# pattern-test-board.net
KiCad netlist of a schematic drawn in EAGLE
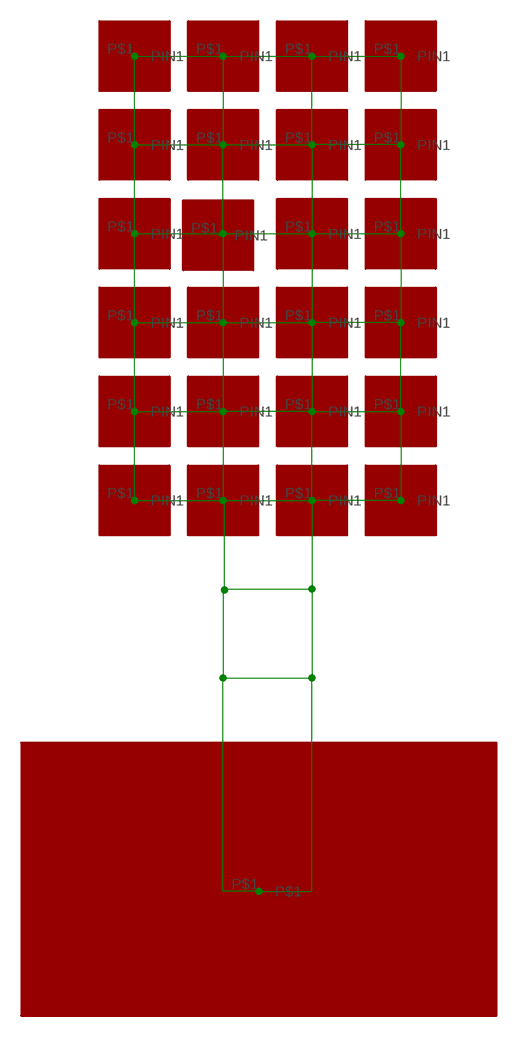
[diagram p0: schematic, sheet 1]

(export (version "E")
  (design (tool "Eeschema 10.0.6"))
  (components
    (comp (ref "U$1")
      (value "TOUCHPIN")
      (footprint "eagle-import:TOUCHPOINT")
      (libsource (lib "eagle-import") (part "TOUCHPIN"))
    )
    (comp (ref "U$2")
      (value "TOUCHPIN")
      (footprint "eagle-import:TOUCHPOINT")
      (libsource (lib "eagle-import") (part "TOUCHPIN"))
    )
    (comp (ref "U$3")
      (value "TOUCHPIN")
      (footprint "eagle-import:TOUCHPOINT")
      (libsource (lib "eagle-import") (part "TOUCHPIN"))
    )
    (comp (ref "U$4")
      (value "TOUCHPIN")
      (footprint "eagle-import:TOUCHPOINT")
      (libsource (lib "eagle-import") (part "TOUCHPIN"))
    )
    (comp (ref "U$5")
      (value "TOUCHPIN")
      (footprint "eagle-import:TOUCHPOINT")
      (libsource (lib "eagle-import") (part "TOUCHPIN"))
    )
    (comp (ref "U$6")
      (value "TOUCHPIN")
      (footprint "eagle-import:TOUCHPOINT")
      (libsource (lib "eagle-import") (part "TOUCHPIN"))
    )
    (comp (ref "U$7")
      (value "TOUCHPIN")
      (footprint "eagle-import:TOUCHPOINT")
      (libsource (lib "eagle-import") (part "TOUCHPIN"))
    )
    (comp (ref "U$8")
      (value "TOUCHPIN")
      (footprint "eagle-import:TOUCHPOINT")
      (libsource (lib "eagle-import") (part "TOUCHPIN"))
    )
    (comp (ref "U$9")
      (value "TOUCHPIN")
      (footprint "eagle-import:TOUCHPOINT")
      (libsource (lib "eagle-import") (part "TOUCHPIN"))
    )
    (comp (ref "U$14")
      (value "TOUCHPIN")
      (footprint "eagle-import:TOUCHPOINT")
      (libsource (lib "eagle-import") (part "TOUCHPIN"))
    )
    (comp (ref "U$15")
      (value "TOUCHPIN")
      (footprint "eagle-import:TOUCHPOINT")
      (libsource (lib "eagle-import") (part "TOUCHPIN"))
    )
    (comp (ref "U$16")
      (value "TOUCHPIN")
      (footprint "eagle-import:TOUCHPOINT")
      (libsource (lib "eagle-import") (part "TOUCHPIN"))
    )
    (comp (ref "U$17")
      (value "TOUCHPIN")
      (footprint "eagle-import:TOUCHPOINT")
      (libsource (lib "eagle-import") (part "TOUCHPIN"))
    )
    (comp (ref "U$18")
      (value "TOUCHPIN")
      (footprint "eagle-import:TOUCHPOINT")
      (libsource (lib "eagle-import") (part "TOUCHPIN"))
    )
    (comp (ref "U$19")
      (value "TOUCHPIN")
      (footprint "eagle-import:TOUCHPOINT")
      (libsource (lib "eagle-import") (part "TOUCHPIN"))
    )
    (comp (ref "U$20")
      (value "TOUCHPIN")
      (footprint "eagle-import:TOUCHPOINT")
      (libsource (lib "eagle-import") (part "TOUCHPIN"))
    )
    (comp (ref "U$21")
      (value "TOUCHPIN")
      (footprint "eagle-import:TOUCHPOINT")
      (libsource (lib "eagle-import") (part "TOUCHPIN"))
    )
    (comp (ref "U$22")
      (value "TOUCHPIN")
      (footprint "eagle-import:TOUCHPOINT")
      (libsource (lib "eagle-import") (part "TOUCHPIN"))
    )
    (comp (ref "U$23")
      (value "TOUCHPIN")
      (footprint "eagle-import:TOUCHPOINT")
      (libsource (lib "eagle-import") (part "TOUCHPIN"))
    )
    (comp (ref "U$28")
      (value "TOUCHPIN")
      (footprint "eagle-import:TOUCHPOINT")
      (libsource (lib "eagle-import") (part "TOUCHPIN"))
    )
    (comp (ref "U$29")
      (value "TOUCHPIN")
      (footprint "eagle-import:TOUCHPOINT")
      (libsource (lib "eagle-import") (part "TOUCHPIN"))
    )
    (comp (ref "U$30")
      (value "TOUCHPIN")
      (footprint "eagle-import:TOUCHPOINT")
      (libsource (lib "eagle-import") (part "TOUCHPIN"))
    )
    (comp (ref "U$31")
      (value "TOUCHPIN")
      (footprint "eagle-import:TOUCHPOINT")
      (libsource (lib "eagle-import") (part "TOUCHPIN"))
    )
    (comp (ref "U$32")
      (value "TOUCHPIN")
      (footprint "eagle-import:TOUCHPOINT")
      (libsource (lib "eagle-import") (part "TOUCHPIN"))
    )
    (comp (ref "U$33")
      (value "TOUCHBASE")
      (footprint "eagle-import:TOUCHBASE")
      (libsource (lib "eagle-import") (part "TOUCHBASE"))
    )
  )
  (nets
    (net (code "1") (name "Net-(U$1-PIN1)") (class "Default")
      (node (ref "U$1") (pin "P$1") (pinfunction "PIN1_P$1") (pintype "bidirectional"))
      (node (ref "U$14") (pin "P$1") (pinfunction "PIN1_P$1") (pintype "bidirectional"))
      (node (ref "U$15") (pin "P$1") (pinfunction "PIN1_P$1") (pintype "bidirectional"))
      (node (ref "U$16") (pin "P$1") (pinfunction "PIN1_P$1") (pintype "bidirectional"))
      (node (ref "U$17") (pin "P$1") (pinfunction "PIN1_P$1") (pintype "bidirectional"))
      (node (ref "U$18") (pin "P$1") (pinfunction "PIN1_P$1") (pintype "bidirectional"))
      (node (ref "U$19") (pin "P$1") (pinfunction "PIN1_P$1") (pintype "bidirectional"))
      (node (ref "U$2") (pin "P$1") (pinfunction "PIN1_P$1") (pintype "bidirectional"))
      (node (ref "U$20") (pin "P$1") (pinfunction "PIN1_P$1") (pintype "bidirectional"))
      (node (ref "U$21") (pin "P$1") (pinfunction "PIN1_P$1") (pintype "bidirectional"))
      (node (ref "U$22") (pin "P$1") (pinfunction "PIN1_P$1") (pintype "bidirectional"))
      (node (ref "U$23") (pin "P$1") (pinfunction "PIN1_P$1") (pintype "bidirectional"))
      (node (ref "U$28") (pin "P$1") (pinfunction "PIN1_P$1") (pintype "bidirectional"))
      (node (ref "U$29") (pin "P$1") (pinfunction "PIN1_P$1") (pintype "bidirectional"))
      (node (ref "U$3") (pin "P$1") (pinfunction "PIN1_P$1") (pintype "bidirectional"))
      (node (ref "U$30") (pin "P$1") (pinfunction "PIN1_P$1") (pintype "bidirectional"))
      (node (ref "U$31") (pin "P$1") (pinfunction "PIN1_P$1") (pintype "bidirectional"))
      (node (ref "U$32") (pin "P$1") (pinfunction "PIN1_P$1") (pintype "bidirectional"))
      (node (ref "U$33") (pin "P$1") (pinfunction "P$1_P$1") (pintype "bidirectional"))
      (node (ref "U$4") (pin "P$1") (pinfunction "PIN1_P$1") (pintype "bidirectional"))
      (node (ref "U$5") (pin "P$1") (pinfunction "PIN1_P$1") (pintype "bidirectional"))
      (node (ref "U$6") (pin "P$1") (pinfunction "PIN1_P$1") (pintype "bidirectional"))
      (node (ref "U$7") (pin "P$1") (pinfunction "PIN1_P$1") (pintype "bidirectional"))
      (node (ref "U$8") (pin "P$1") (pinfunction "PIN1_P$1") (pintype "bidirectional"))
      (node (ref "U$9") (pin "P$1") (pinfunction "PIN1_P$1") (pintype "bidirectional"))
    )
  )
)
